# protoBoardHB.net
KiCad netlist of a schematic drawn in EAGLE
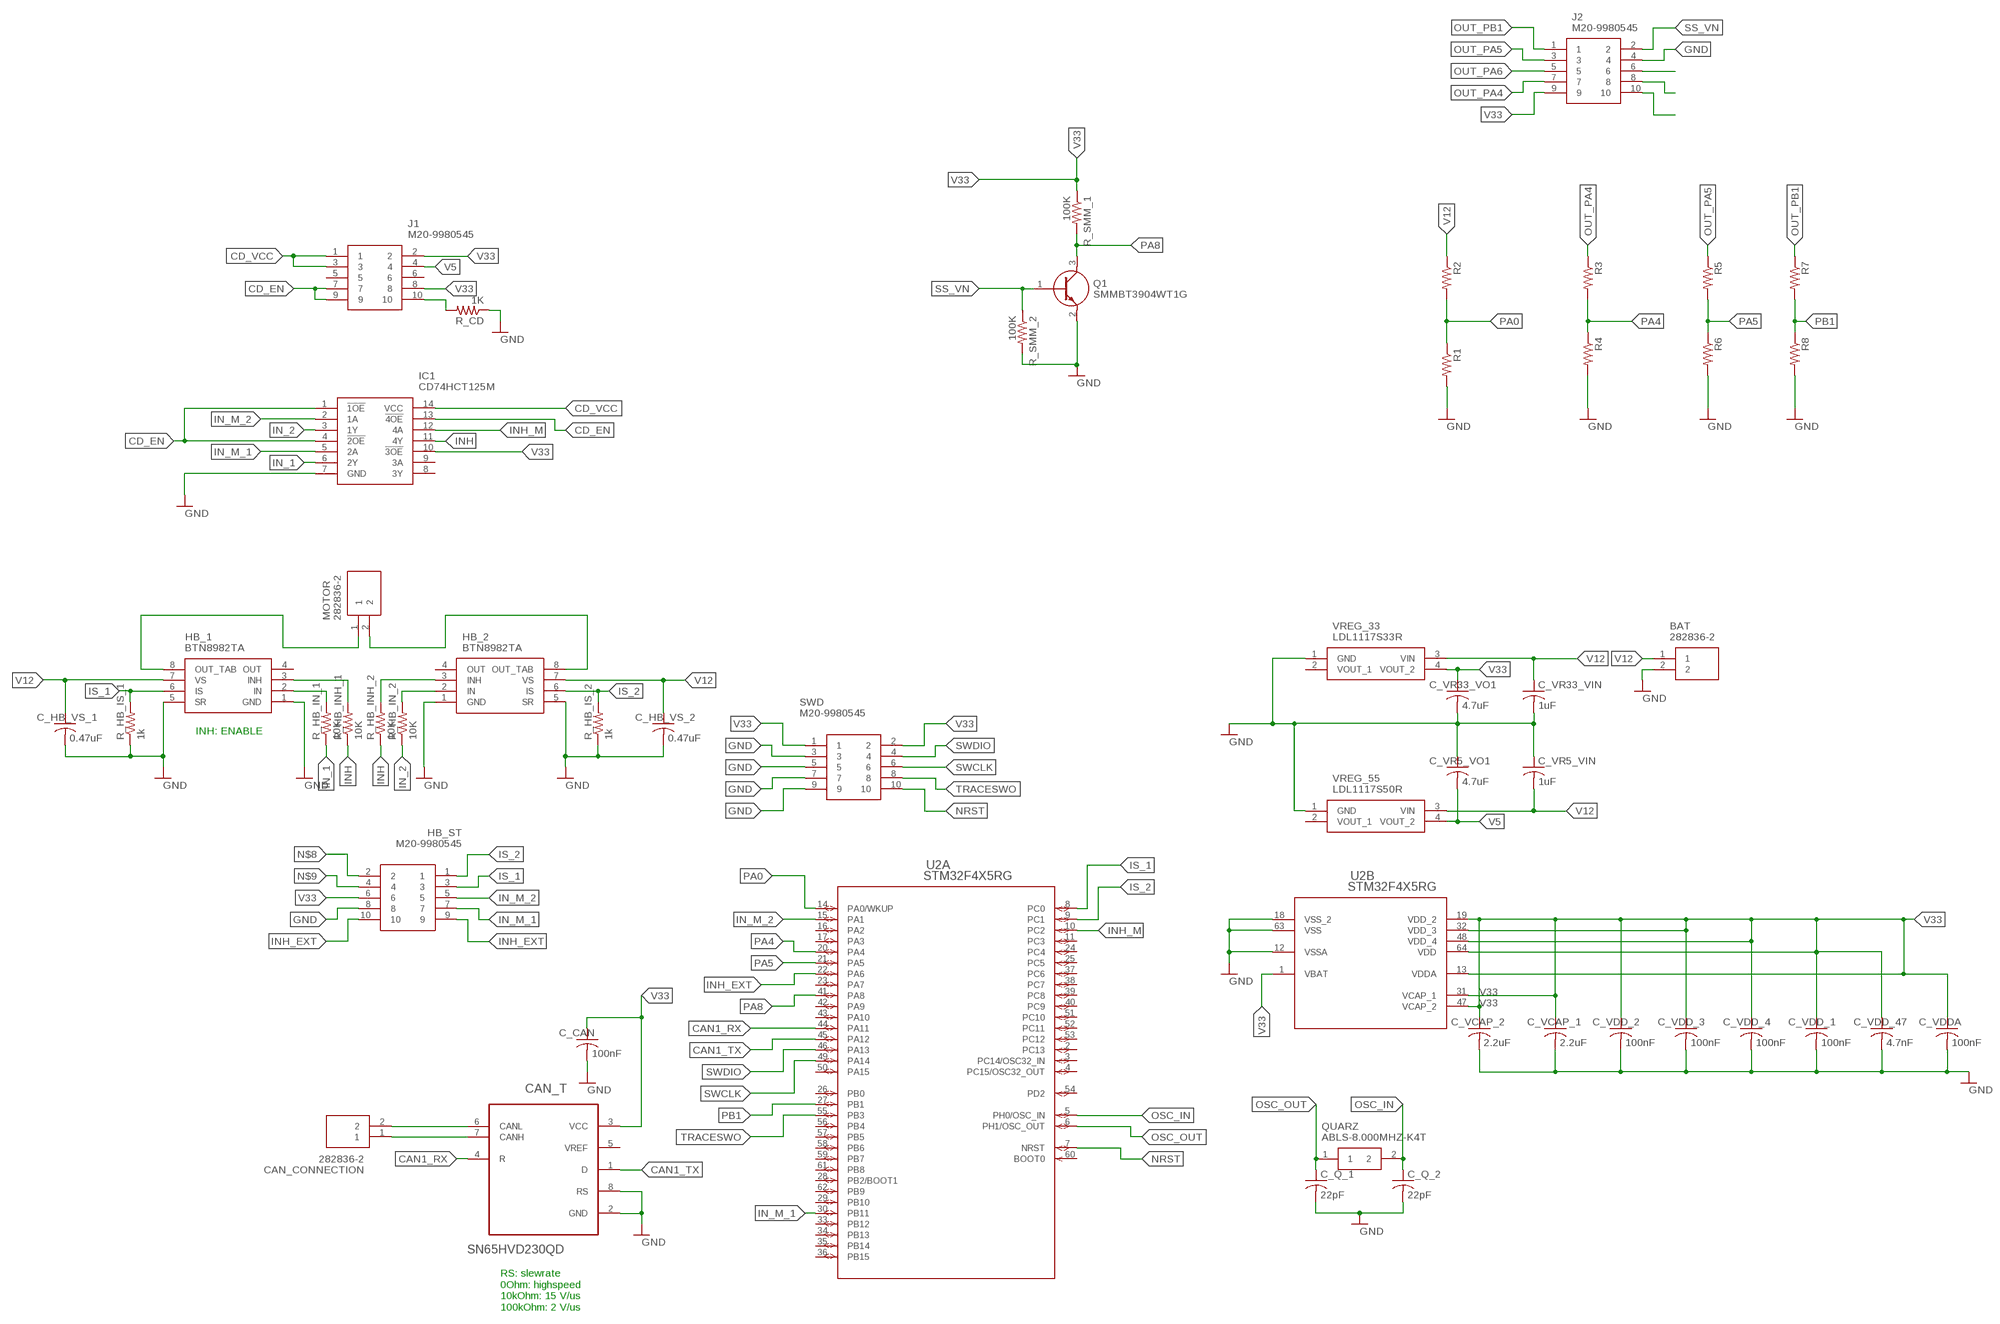
[diagram p0: schematic, sheet 1]

(export (version "E")
  (design (tool "Eeschema 10.0.6"))
  (components
    (comp (ref "BAT")
      (value "282836-2")
      (footprint "eagle-import:SHDR2W100P0X500_1X2_1000X820X1")
      (fields (field (name "MOUSER_PART_NUMBER") "571-2828362"))
      (libsource (lib "eagle-import") (part "282836-2"))
    )
    (comp (ref "CAN_CONNECTION")
      (value "282836-2")
      (footprint "eagle-import:SHDR2W100P0X500_1X2_1000X820X1")
      (fields (field (name "MOUSER_PART_NUMBER") "571-2828362"))
      (libsource (lib "eagle-import") (part "282836-2"))
    )
    (comp (ref "CAN_T")
      (value "SN65HVD230QD")
      (footprint "eagle-import:SOIC127P600X175-8N")
      (fields (field (name "MF") "TEXAS INSTRUMENTS") (field (name "MPN") "SN65HVD230QD.."))
      (libsource (lib "eagle-import") (part "SN65HVD230QD"))
    )
    (comp (ref "C_CAN")
      (value "100nF")
      (footprint "eagle-import:C1206")
      (libsource (lib "eagle-import") (part "C-USC1206"))
    )
    (comp (ref "C_HB_VS_1")
      (value "0.47uF")
      (footprint "eagle-import:C1206")
      (libsource (lib "eagle-import") (part "C-USC1206"))
    )
    (comp (ref "C_HB_VS_2")
      (value "0.47uF")
      (footprint "eagle-import:C1206")
      (libsource (lib "eagle-import") (part "C-USC1206"))
    )
    (comp (ref "C_Q_1")
      (value "22pF")
      (footprint "eagle-import:C0805")
      (libsource (lib "eagle-import") (part "C-USC0805"))
    )
    (comp (ref "C_Q_2")
      (value "22pF")
      (footprint "eagle-import:C0805")
      (libsource (lib "eagle-import") (part "C-USC0805"))
    )
    (comp (ref "C_VCAP_1")
      (value "2.2uF")
      (footprint "eagle-import:C1206")
      (libsource (lib "eagle-import") (part "C-USC1206"))
    )
    (comp (ref "C_VCAP_2")
      (value "2.2uF")
      (footprint "eagle-import:C1206")
      (libsource (lib "eagle-import") (part "C-USC1206"))
    )
    (comp (ref "C_VDDA")
      (value "100nF")
      (footprint "eagle-import:C1206")
      (libsource (lib "eagle-import") (part "C-USC1206"))
    )
    (comp (ref "C_VDD_1")
      (value "100nF")
      (footprint "eagle-import:C1206")
      (libsource (lib "eagle-import") (part "C-USC1206"))
    )
    (comp (ref "C_VDD_2")
      (value "100nF")
      (footprint "eagle-import:C1206")
      (libsource (lib "eagle-import") (part "C-USC1206"))
    )
    (comp (ref "C_VDD_3")
      (value "100nF")
      (footprint "eagle-import:C1206")
      (libsource (lib "eagle-import") (part "C-USC1206"))
    )
    (comp (ref "C_VDD_4")
      (value "100nF")
      (footprint "eagle-import:C1206")
      (libsource (lib "eagle-import") (part "C-USC1206"))
    )
    (comp (ref "C_VDD_47")
      (value "4.7nF")
      (footprint "eagle-import:C1206")
      (libsource (lib "eagle-import") (part "C-USC1206"))
    )
    (comp (ref "C_VR5_VIN")
      (value "1uF")
      (footprint "eagle-import:C1206")
      (libsource (lib "eagle-import") (part "C-USC1206"))
    )
    (comp (ref "C_VR5_VO1")
      (value "4.7uF")
      (footprint "eagle-import:C1206")
      (libsource (lib "eagle-import") (part "C-USC1206"))
    )
    (comp (ref "C_VR33_VIN")
      (value "1uF")
      (footprint "eagle-import:C1206")
      (libsource (lib "eagle-import") (part "C-USC1206"))
    )
    (comp (ref "C_VR33_VO1")
      (value "4.7uF")
      (footprint "eagle-import:C1206")
      (libsource (lib "eagle-import") (part "C-USC1206"))
    )
    (comp (ref "HB_1")
      (value "BTN8982TA")
      (footprint "eagle-import:TO127P1500X440-8N")
      (fields (field (name "MOUSER_PART_NUMBER") "726-BTN8982TA"))
      (libsource (lib "eagle-import") (part "BTN8982TA"))
    )
    (comp (ref "HB_2")
      (value "BTN8982TA")
      (footprint "eagle-import:TO127P1500X440-8N")
      (fields (field (name "MOUSER_PART_NUMBER") "726-BTN8982TA"))
      (libsource (lib "eagle-import") (part "BTN8982TA"))
    )
    (comp (ref "HB_ST")
      (value "M20-9980545")
      (footprint "eagle-import:HDRV10W80P254_2X5_1270X508X864")
      (fields (field (name "MOUSER_PART_NUMBER") "855-M20-9980545") (field (name "MF") "HARWIN"))
      (libsource (lib "eagle-import") (part "M20-9980545"))
    )
    (comp (ref "IC1")
      (value "CD74HCT125M")
      (footprint "eagle-import:SOIC127P600X175-14N")
      (fields (field (name "MOUSER_PART_NUMBER") "595-CD74HCT125M"))
      (libsource (lib "eagle-import") (part "CD74HCT125M"))
    )
    (comp (ref "J1")
      (value "M20-9980545")
      (footprint "eagle-import:HDRV10W80P254_2X5_1270X508X864")
      (fields (field (name "MOUSER_PART_NUMBER") "855-M20-9980545"))
      (libsource (lib "eagle-import") (part "M20-9980545"))
    )
    (comp (ref "J2")
      (value "M20-9980545")
      (footprint "eagle-import:HDRV10W80P254_2X5_1270X508X864")
      (fields (field (name "MOUSER_PART_NUMBER") "855-M20-9980545"))
      (libsource (lib "eagle-import") (part "M20-9980545"))
    )
    (comp (ref "MOTOR")
      (value "282836-2")
      (footprint "eagle-import:SHDR2W100P0X500_1X2_1000X820X1")
      (fields (field (name "MOUSER_PART_NUMBER") "571-2828362"))
      (libsource (lib "eagle-import") (part "282836-2"))
    )
    (comp (ref "Q1")
      (value "SMMBT3904WT1G")
      (footprint "eagle-import:SOT65P220X100-3N")
      (fields (field (name "MOUSER_PART_NUMBER") "863-SMMBT3904WT1G"))
      (libsource (lib "eagle-import") (part "SMMBT3904WT1G"))
    )
    (comp (ref "QUARZ")
      (value "ABLS-8.000MHZ-K4T")
      (footprint "eagle-import:ABLS-12.000MHZ-B2")
      (fields (field (name "MOUSER_PART_NUMBER") "815-ABLS-8.0MK4-T") (field (name "MF") "ABRACON"))
      (libsource (lib "eagle-import") (part "ABLS-8.000MHZ-K4T"))
    )
    (comp (ref "R1")
      (value "R-US_R1206")
      (footprint "eagle-import:R1206")
      (libsource (lib "eagle-import") (part "R-US_R1206"))
    )
    (comp (ref "R2")
      (value "R-US_R1206")
      (footprint "eagle-import:R1206")
      (libsource (lib "eagle-import") (part "R-US_R1206"))
    )
    (comp (ref "R3")
      (value "R-US_R1206")
      (footprint "eagle-import:R1206")
      (libsource (lib "eagle-import") (part "R-US_R1206"))
    )
    (comp (ref "R4")
      (value "R-US_R1206")
      (footprint "eagle-import:R1206")
      (libsource (lib "eagle-import") (part "R-US_R1206"))
    )
    (comp (ref "R5")
      (value "R-US_R1206")
      (footprint "eagle-import:R1206")
      (libsource (lib "eagle-import") (part "R-US_R1206"))
    )
    (comp (ref "R6")
      (value "R-US_R1206")
      (footprint "eagle-import:R1206")
      (libsource (lib "eagle-import") (part "R-US_R1206"))
    )
    (comp (ref "R7")
      (value "R-US_R1206")
      (footprint "eagle-import:R1206")
      (libsource (lib "eagle-import") (part "R-US_R1206"))
    )
    (comp (ref "R8")
      (value "R-US_R1206")
      (footprint "eagle-import:R1206")
      (libsource (lib "eagle-import") (part "R-US_R1206"))
    )
    (comp (ref "R_CD")
      (value "1K")
      (footprint "eagle-import:R1206")
      (libsource (lib "eagle-import") (part "R-US_R1206"))
    )
    (comp (ref "R_HB_INH_1")
      (value "10K")
      (footprint "eagle-import:R1206")
      (libsource (lib "eagle-import") (part "R-US_R1206"))
    )
    (comp (ref "R_HB_INH_2")
      (value "10K")
      (footprint "eagle-import:R1206")
      (libsource (lib "eagle-import") (part "R-US_R1206"))
    )
    (comp (ref "R_HB_IN_1")
      (value "10K")
      (footprint "eagle-import:R1206")
      (libsource (lib "eagle-import") (part "R-US_R1206"))
    )
    (comp (ref "R_HB_IN_2")
      (value "10K")
      (footprint "eagle-import:R1206")
      (libsource (lib "eagle-import") (part "R-US_R1206"))
    )
    (comp (ref "R_HB_IS_1")
      (value "1k")
      (footprint "eagle-import:R1206")
      (libsource (lib "eagle-import") (part "R-US_R1206"))
    )
    (comp (ref "R_HB_IS_2")
      (value "1k")
      (footprint "eagle-import:R1206")
      (libsource (lib "eagle-import") (part "R-US_R1206"))
    )
    (comp (ref "R_SMM_1")
      (value "100K")
      (footprint "eagle-import:R1206")
      (libsource (lib "eagle-import") (part "R-US_R1206"))
    )
    (comp (ref "R_SMM_2")
      (value "100K")
      (footprint "eagle-import:R1206")
      (libsource (lib "eagle-import") (part "R-US_R1206"))
    )
    (comp (ref "SWD")
      (value "M20-9980545")
      (footprint "eagle-import:HDRV10W80P254_2X5_1270X508X864")
      (fields (field (name "MOUSER_PART_NUMBER") "855-M20-9980545") (field (name "MF") "HARWIN"))
      (libsource (lib "eagle-import") (part "M20-9980545"))
    )
    (comp (ref "U2")
      (value "STM32F4X5RG")
      (footprint "eagle-import:LQFP64-10X10MM")
      (fields (field (name "OC_FARNELL") "unknown"))
      (libsource (lib "eagle-import") (part "STM32F4X5RG"))
    )
    (comp (ref "VREG_33")
      (value "LDL1117S33R")
      (footprint "eagle-import:SOT230P700X180-4N")
      (fields (field (name "MOUSER_PART_NUMBER") "511-LDL1117S33R") (field (name "MF") "STMICROELECTRONICS"))
      (libsource (lib "eagle-import") (part "LDL1117S33R"))
    )
    (comp (ref "VREG_55")
      (value "LDL1117S50R")
      (footprint "eagle-import:SOT230P700X180-4N")
      (fields (field (name "MOUSER_PART_NUMBER") "511-LDL1117S50R") (field (name "MF") "STMICROELECTRONICS"))
      (libsource (lib "eagle-import") (part "LDL1117S50R"))
    )
  )
  (nets
    (net (code "1") (name "CAN1_RX") (class "Default")
      (node (ref "CAN_T") (pin "4") (pinfunction "R_4") (pintype "output"))
      (node (ref "U2") (pin "44") (pinfunction "PA11_44") (pintype "bidirectional"))
    )
    (net (code "2") (name "CAN1_TX") (class "Default")
      (node (ref "CAN_T") (pin "1") (pinfunction "D_1") (pintype "input"))
      (node (ref "U2") (pin "45") (pinfunction "PA12_45") (pintype "bidirectional"))
    )
    (net (code "3") (name "CD_EN") (class "Default")
      (node (ref "IC1") (pin "1") (pinfunction "~{1OE}_1") (pintype "bidirectional"))
      (node (ref "IC1") (pin "13") (pinfunction "~{4OE}_13") (pintype "bidirectional"))
      (node (ref "IC1") (pin "4") (pinfunction "~{2OE}_4") (pintype "bidirectional"))
      (node (ref "J1") (pin "7") (pinfunction "7_7") (pintype "bidirectional"))
      (node (ref "J1") (pin "9") (pinfunction "9_9") (pintype "bidirectional"))
    )
    (net (code "4") (name "CD_VCC") (class "Default")
      (node (ref "IC1") (pin "14") (pinfunction "VCC_14") (pintype "power_in"))
      (node (ref "J1") (pin "1") (pinfunction "1_1") (pintype "bidirectional"))
      (node (ref "J1") (pin "3") (pinfunction "3_3") (pintype "bidirectional"))
    )
    (net (code "5") (name "GND") (class "Default")
      (node (ref "BAT") (pin "2") (pinfunction "2_2") (pintype "bidirectional"))
      (node (ref "CAN_T") (pin "2") (pinfunction "GND_2") (pintype "passive"))
      (node (ref "CAN_T") (pin "8") (pinfunction "RS_8") (pintype "input"))
      (node (ref "C_CAN") (pin "2") (pinfunction "2_2") (pintype "passive"))
      (node (ref "C_HB_VS_1") (pin "2") (pinfunction "2_2") (pintype "passive"))
      (node (ref "C_HB_VS_2") (pin "2") (pinfunction "2_2") (pintype "passive"))
      (node (ref "C_Q_1") (pin "2") (pinfunction "2_2") (pintype "passive"))
      (node (ref "C_Q_2") (pin "2") (pinfunction "2_2") (pintype "passive"))
      (node (ref "C_VCAP_1") (pin "2") (pinfunction "2_2") (pintype "passive"))
      (node (ref "C_VCAP_2") (pin "2") (pinfunction "2_2") (pintype "passive"))
      (node (ref "C_VDDA") (pin "2") (pinfunction "2_2") (pintype "passive"))
      (node (ref "C_VDD_1") (pin "2") (pinfunction "2_2") (pintype "passive"))
      (node (ref "C_VDD_2") (pin "2") (pinfunction "2_2") (pintype "passive"))
      (node (ref "C_VDD_3") (pin "2") (pinfunction "2_2") (pintype "passive"))
      (node (ref "C_VDD_4") (pin "2") (pinfunction "2_2") (pintype "passive"))
      (node (ref "C_VDD_47") (pin "2") (pinfunction "2_2") (pintype "passive"))
      (node (ref "C_VR33_VIN") (pin "2") (pinfunction "2_2") (pintype "passive"))
      (node (ref "C_VR33_VO1") (pin "2") (pinfunction "2_2") (pintype "passive"))
      (node (ref "C_VR5_VIN") (pin "1") (pinfunction "1_1") (pintype "passive"))
      (node (ref "C_VR5_VO1") (pin "1") (pinfunction "1_1") (pintype "passive"))
      (node (ref "HB_1") (pin "1") (pinfunction "GND_1") (pintype "power_in"))
      (node (ref "HB_1") (pin "5") (pinfunction "SR_5") (pintype "bidirectional"))
      (node (ref "HB_2") (pin "1") (pinfunction "GND_1") (pintype "power_in"))
      (node (ref "HB_2") (pin "5") (pinfunction "SR_5") (pintype "bidirectional"))
      (node (ref "HB_ST") (pin "8") (pinfunction "8_8") (pintype "bidirectional"))
      (node (ref "IC1") (pin "7") (pinfunction "GND_7") (pintype "power_in"))
      (node (ref "J2") (pin "4") (pinfunction "4_4") (pintype "bidirectional"))
      (node (ref "Q1") (pin "2") (pinfunction "E_2") (pintype "bidirectional"))
      (node (ref "R1") (pin "2") (pinfunction "2_2") (pintype "passive"))
      (node (ref "R4") (pin "2") (pinfunction "2_2") (pintype "passive"))
      (node (ref "R6") (pin "2") (pinfunction "2_2") (pintype "passive"))
      (node (ref "R8") (pin "2") (pinfunction "2_2") (pintype "passive"))
      (node (ref "R_CD") (pin "1") (pinfunction "1_1") (pintype "passive"))
      (node (ref "R_HB_IS_1") (pin "1") (pinfunction "1_1") (pintype "passive"))
      (node (ref "R_HB_IS_2") (pin "1") (pinfunction "1_1") (pintype "passive"))
      (node (ref "R_SMM_2") (pin "2") (pinfunction "2_2") (pintype "passive"))
      (node (ref "SWD") (pin "3") (pinfunction "3_3") (pintype "bidirectional"))
      (node (ref "SWD") (pin "5") (pinfunction "5_5") (pintype "bidirectional"))
      (node (ref "SWD") (pin "7") (pinfunction "7_7") (pintype "bidirectional"))
      (node (ref "SWD") (pin "9") (pinfunction "9_9") (pintype "bidirectional"))
      (node (ref "U2") (pin "12") (pinfunction "VSSA_12") (pintype "power_in"))
      (node (ref "U2") (pin "18") (pinfunction "VSS_2_18") (pintype "power_in"))
      (node (ref "U2") (pin "63") (pinfunction "VSS_63") (pintype "power_in"))
      (node (ref "VREG_33") (pin "1") (pinfunction "GND_1") (pintype "power_in"))
      (node (ref "VREG_55") (pin "1") (pinfunction "GND_1") (pintype "bidirectional"))
    )
    (net (code "6") (name "INH") (class "Default")
      (node (ref "IC1") (pin "11") (pinfunction "4Y_11") (pintype "bidirectional"))
      (node (ref "R_HB_INH_1") (pin "1") (pinfunction "1_1") (pintype "passive"))
      (node (ref "R_HB_INH_2") (pin "1") (pinfunction "1_1") (pintype "passive"))
    )
    (net (code "7") (name "INH_EXT") (class "Default")
      (node (ref "HB_ST") (pin "10") (pinfunction "10_10") (pintype "bidirectional"))
      (node (ref "HB_ST") (pin "9") (pinfunction "9_9") (pintype "bidirectional"))
      (node (ref "U2") (pin "22") (pinfunction "PA6_22") (pintype "bidirectional"))
    )
    (net (code "8") (name "INH_M") (class "Default")
      (node (ref "IC1") (pin "12") (pinfunction "4A_12") (pintype "bidirectional"))
      (node (ref "U2") (pin "10") (pinfunction "PC2_10") (pintype "bidirectional"))
    )
    (net (code "9") (name "IN_1") (class "Default")
      (node (ref "IC1") (pin "6") (pinfunction "2Y_6") (pintype "bidirectional"))
      (node (ref "R_HB_IN_1") (pin "1") (pinfunction "1_1") (pintype "passive"))
    )
    (net (code "10") (name "IN_2") (class "Default")
      (node (ref "IC1") (pin "3") (pinfunction "1Y_3") (pintype "bidirectional"))
      (node (ref "R_HB_IN_2") (pin "1") (pinfunction "1_1") (pintype "passive"))
    )
    (net (code "11") (name "IN_M_1") (class "Default")
      (node (ref "HB_ST") (pin "7") (pinfunction "7_7") (pintype "bidirectional"))
      (node (ref "IC1") (pin "5") (pinfunction "2A_5") (pintype "bidirectional"))
      (node (ref "U2") (pin "30") (pinfunction "PB11_30") (pintype "bidirectional"))
    )
    (net (code "12") (name "IN_M_2") (class "Default")
      (node (ref "HB_ST") (pin "5") (pinfunction "5_5") (pintype "bidirectional"))
      (node (ref "IC1") (pin "2") (pinfunction "1A_2") (pintype "bidirectional"))
      (node (ref "U2") (pin "15") (pinfunction "PA1_15") (pintype "bidirectional"))
    )
    (net (code "13") (name "IS_1") (class "Default")
      (node (ref "HB_1") (pin "6") (pinfunction "IS_6") (pintype "bidirectional"))
      (node (ref "HB_ST") (pin "3") (pinfunction "3_3") (pintype "bidirectional"))
      (node (ref "R_HB_IS_1") (pin "2") (pinfunction "2_2") (pintype "passive"))
      (node (ref "U2") (pin "8") (pinfunction "PC0_8") (pintype "bidirectional"))
    )
    (net (code "14") (name "IS_2") (class "Default")
      (node (ref "HB_2") (pin "6") (pinfunction "IS_6") (pintype "bidirectional"))
      (node (ref "HB_ST") (pin "1") (pinfunction "1_1") (pintype "bidirectional"))
      (node (ref "R_HB_IS_2") (pin "2") (pinfunction "2_2") (pintype "passive"))
      (node (ref "U2") (pin "9") (pinfunction "PC1_9") (pintype "bidirectional"))
    )
    (net (code "15") (name "N$8") (class "Default")
      (node (ref "HB_ST") (pin "2") (pinfunction "2_2") (pintype "bidirectional"))
    )
    (net (code "16") (name "N$9") (class "Default")
      (node (ref "HB_ST") (pin "4") (pinfunction "4_4") (pintype "bidirectional"))
    )
    (net (code "17") (name "NRST") (class "Default")
      (node (ref "SWD") (pin "10") (pinfunction "10_10") (pintype "bidirectional"))
      (node (ref "U2") (pin "7") (pinfunction "NRST_7") (pintype "bidirectional"))
    )
    (net (code "18") (name "Net-(CAN_T-CANH)") (class "Default")
      (node (ref "CAN_CONNECTION") (pin "1") (pinfunction "1_1") (pintype "bidirectional"))
      (node (ref "CAN_T") (pin "7") (pinfunction "CANH_7") (pintype "output"))
    )
    (net (code "19") (name "Net-(CAN_T-CANL)") (class "Default")
      (node (ref "CAN_CONNECTION") (pin "2") (pinfunction "2_2") (pintype "bidirectional"))
      (node (ref "CAN_T") (pin "6") (pinfunction "CANL_6") (pintype "output"))
    )
    (net (code "20") (name "Net-(HB_1-IN)") (class "Default")
      (node (ref "HB_1") (pin "2") (pinfunction "IN_2") (pintype "input"))
      (node (ref "R_HB_IN_1") (pin "2") (pinfunction "2_2") (pintype "passive"))
    )
    (net (code "21") (name "Net-(HB_1-INH)") (class "Default")
      (node (ref "HB_1") (pin "3") (pinfunction "INH_3") (pintype "input"))
      (node (ref "R_HB_INH_1") (pin "2") (pinfunction "2_2") (pintype "passive"))
    )
    (net (code "22") (name "Net-(HB_1-OUT_TAB)") (class "Default")
      (node (ref "HB_1") (pin "8") (pinfunction "OUT_TAB_8") (pintype "output"))
      (node (ref "MOTOR") (pin "1") (pinfunction "1_1") (pintype "bidirectional"))
    )
    (net (code "23") (name "Net-(HB_2-IN)") (class "Default")
      (node (ref "HB_2") (pin "2") (pinfunction "IN_2") (pintype "input"))
      (node (ref "R_HB_IN_2") (pin "2") (pinfunction "2_2") (pintype "passive"))
    )
    (net (code "24") (name "Net-(HB_2-INH)") (class "Default")
      (node (ref "HB_2") (pin "3") (pinfunction "INH_3") (pintype "input"))
      (node (ref "R_HB_INH_2") (pin "2") (pinfunction "2_2") (pintype "passive"))
    )
    (net (code "25") (name "Net-(HB_2-OUT_TAB)") (class "Default")
      (node (ref "HB_2") (pin "8") (pinfunction "OUT_TAB_8") (pintype "output"))
      (node (ref "MOTOR") (pin "2") (pinfunction "2_2") (pintype "bidirectional"))
    )
    (net (code "26") (name "Net-(J1-Pad10)") (class "Default")
      (node (ref "J1") (pin "10") (pinfunction "10_10") (pintype "bidirectional"))
      (node (ref "R_CD") (pin "2") (pinfunction "2_2") (pintype "passive"))
    )
    (net (code "27") (name "OSC_IN") (class "Default")
      (node (ref "C_Q_2") (pin "1") (pinfunction "1_1") (pintype "passive"))
      (node (ref "QUARZ") (pin "2") (pinfunction "2_2") (pintype "bidirectional"))
      (node (ref "U2") (pin "5") (pinfunction "PH0/OSC_IN_5") (pintype "bidirectional"))
    )
    (net (code "28") (name "OSC_OUT") (class "Default")
      (node (ref "C_Q_1") (pin "1") (pinfunction "1_1") (pintype "passive"))
      (node (ref "QUARZ") (pin "1") (pinfunction "1_1") (pintype "bidirectional"))
      (node (ref "U2") (pin "6") (pinfunction "PH1/OSC_OUT_6") (pintype "bidirectional"))
    )
    (net (code "29") (name "OUT_PA4") (class "Default")
      (node (ref "J2") (pin "7") (pinfunction "7_7") (pintype "bidirectional"))
      (node (ref "R3") (pin "1") (pinfunction "1_1") (pintype "passive"))
    )
    (net (code "30") (name "OUT_PA5") (class "Default")
      (node (ref "J2") (pin "3") (pinfunction "3_3") (pintype "bidirectional"))
      (node (ref "R5") (pin "1") (pinfunction "1_1") (pintype "passive"))
    )
    (net (code "31") (name "OUT_PA6") (class "Default")
      (node (ref "J2") (pin "5") (pinfunction "5_5") (pintype "bidirectional"))
    )
    (net (code "32") (name "OUT_PB1") (class "Default")
      (node (ref "J2") (pin "1") (pinfunction "1_1") (pintype "bidirectional"))
      (node (ref "R7") (pin "1") (pinfunction "1_1") (pintype "passive"))
    )
    (net (code "33") (name "PA0") (class "Default")
      (node (ref "R1") (pin "1") (pinfunction "1_1") (pintype "passive"))
      (node (ref "R2") (pin "2") (pinfunction "2_2") (pintype "passive"))
      (node (ref "U2") (pin "14") (pinfunction "PA0/WKUP_14") (pintype "bidirectional"))
    )
    (net (code "34") (name "PA4") (class "Default")
      (node (ref "R3") (pin "2") (pinfunction "2_2") (pintype "passive"))
      (node (ref "R4") (pin "1") (pinfunction "1_1") (pintype "passive"))
      (node (ref "U2") (pin "20") (pinfunction "PA4_20") (pintype "bidirectional"))
    )
    (net (code "35") (name "PA5") (class "Default")
      (node (ref "R5") (pin "2") (pinfunction "2_2") (pintype "passive"))
      (node (ref "R6") (pin "1") (pinfunction "1_1") (pintype "passive"))
      (node (ref "U2") (pin "21") (pinfunction "PA5_21") (pintype "bidirectional"))
    )
    (net (code "36") (name "PA8") (class "Default")
      (node (ref "Q1") (pin "3") (pinfunction "C_3") (pintype "bidirectional"))
      (node (ref "R_SMM_1") (pin "2") (pinfunction "2_2") (pintype "passive"))
      (node (ref "U2") (pin "41") (pinfunction "PA8_41") (pintype "bidirectional"))
    )
    (net (code "37") (name "PB1") (class "Default")
      (node (ref "R7") (pin "2") (pinfunction "2_2") (pintype "passive"))
      (node (ref "R8") (pin "1") (pinfunction "1_1") (pintype "passive"))
      (node (ref "U2") (pin "27") (pinfunction "PB1_27") (pintype "bidirectional"))
    )
    (net (code "38") (name "SS_VN") (class "Default")
      (node (ref "J2") (pin "2") (pinfunction "2_2") (pintype "bidirectional"))
      (node (ref "Q1") (pin "1") (pinfunction "B_1") (pintype "bidirectional"))
      (node (ref "R_SMM_2") (pin "1") (pinfunction "1_1") (pintype "passive"))
    )
    (net (code "39") (name "SWCLK") (class "Default")
      (node (ref "SWD") (pin "6") (pinfunction "6_6") (pintype "bidirectional"))
      (node (ref "U2") (pin "49") (pinfunction "PA14_49") (pintype "bidirectional"))
    )
    (net (code "40") (name "SWDIO") (class "Default")
      (node (ref "SWD") (pin "4") (pinfunction "4_4") (pintype "bidirectional"))
      (node (ref "U2") (pin "46") (pinfunction "PA13_46") (pintype "bidirectional"))
    )
    (net (code "41") (name "TRACESWO") (class "Default")
      (node (ref "SWD") (pin "8") (pinfunction "8_8") (pintype "bidirectional"))
      (node (ref "U2") (pin "55") (pinfunction "PB3_55") (pintype "bidirectional"))
    )
    (net (code "42") (name "V5") (class "Default")
      (node (ref "C_VR5_VO1") (pin "2") (pinfunction "2_2") (pintype "passive"))
      (node (ref "J1") (pin "4") (pinfunction "4_4") (pintype "bidirectional"))
      (node (ref "VREG_55") (pin "4") (pinfunction "VOUT_2_4") (pintype "bidirectional"))
    )
    (net (code "43") (name "V12") (class "Default")
      (node (ref "BAT") (pin "1") (pinfunction "1_1") (pintype "bidirectional"))
      (node (ref "C_HB_VS_1") (pin "1") (pinfunction "1_1") (pintype "passive"))
      (node (ref "C_HB_VS_2") (pin "1") (pinfunction "1_1") (pintype "passive"))
      (node (ref "C_VR33_VIN") (pin "1") (pinfunction "1_1") (pintype "passive"))
      (node (ref "C_VR5_VIN") (pin "2") (pinfunction "2_2") (pintype "passive"))
      (node (ref "HB_1") (pin "7") (pinfunction "VS_7") (pintype "bidirectional"))
      (node (ref "HB_2") (pin "7") (pinfunction "VS_7") (pintype "bidirectional"))
      (node (ref "R2") (pin "1") (pinfunction "1_1") (pintype "passive"))
      (node (ref "VREG_33") (pin "3") (pinfunction "VIN_3") (pintype "input"))
      (node (ref "VREG_55") (pin "3") (pinfunction "VIN_3") (pintype "bidirectional"))
    )
    (net (code "44") (name "V33") (class "Default")
      (node (ref "CAN_T") (pin "3") (pinfunction "VCC_3") (pintype "power_in"))
      (node (ref "C_CAN") (pin "1") (pinfunction "1_1") (pintype "passive"))
      (node (ref "C_VCAP_1") (pin "1") (pinfunction "1_1") (pintype "passive"))
      (node (ref "C_VCAP_2") (pin "1") (pinfunction "1_1") (pintype "passive"))
      (node (ref "C_VDDA") (pin "1") (pinfunction "1_1") (pintype "passive"))
      (node (ref "C_VDD_1") (pin "1") (pinfunction "1_1") (pintype "passive"))
      (node (ref "C_VDD_2") (pin "1") (pinfunction "1_1") (pintype "passive"))
      (node (ref "C_VDD_3") (pin "1") (pinfunction "1_1") (pintype "passive"))
      (node (ref "C_VDD_4") (pin "1") (pinfunction "1_1") (pintype "passive"))
      (node (ref "C_VDD_47") (pin "1") (pinfunction "1_1") (pintype "passive"))
      (node (ref "C_VR33_VO1") (pin "1") (pinfunction "1_1") (pintype "passive"))
      (node (ref "HB_ST") (pin "6") (pinfunction "6_6") (pintype "bidirectional"))
      (node (ref "IC1") (pin "10") (pinfunction "~{3OE}_10") (pintype "bidirectional"))
      (node (ref "J1") (pin "2") (pinfunction "2_2") (pintype "bidirectional"))
      (node (ref "J1") (pin "8") (pinfunction "8_8") (pintype "bidirectional"))
      (node (ref "J2") (pin "9") (pinfunction "9_9") (pintype "bidirectional"))
      (node (ref "R_SMM_1") (pin "1") (pinfunction "1_1") (pintype "passive"))
      (node (ref "SWD") (pin "1") (pinfunction "1_1") (pintype "bidirectional"))
      (node (ref "SWD") (pin "2") (pinfunction "2_2") (pintype "bidirectional"))
      (node (ref "U2") (pin "1") (pinfunction "VBAT_1") (pintype "power_in"))
      (node (ref "U2") (pin "13") (pinfunction "VDDA_13") (pintype "power_in"))
      (node (ref "U2") (pin "19") (pinfunction "VDD_2_19") (pintype "power_in"))
      (node (ref "U2") (pin "31") (pinfunction "VCAP_1_31") (pintype "power_in"))
      (node (ref "U2") (pin "32") (pinfunction "VDD_3_32") (pintype "power_in"))
      (node (ref "U2") (pin "47") (pinfunction "VCAP_2_47") (pintype "power_in"))
      (node (ref "U2") (pin "48") (pinfunction "VDD_4_48") (pintype "power_in"))
      (node (ref "U2") (pin "64") (pinfunction "VDD_64") (pintype "power_in"))
      (node (ref "VREG_33") (pin "4") (pinfunction "VOUT_2_4") (pintype "output"))
    )
    (net (code "45") (name "unconnected-(CAN_T-VREF-Pad5)") (class "Default")
      (node (ref "CAN_T") (pin "5") (pinfunction "VREF_5") (pintype "input"))
    )
    (net (code "46") (name "unconnected-(HB_1-OUT-Pad4)") (class "Default")
      (node (ref "HB_1") (pin "4") (pinfunction "OUT_4") (pintype "output"))
    )
    (net (code "47") (name "unconnected-(HB_2-OUT-Pad4)") (class "Default")
      (node (ref "HB_2") (pin "4") (pinfunction "OUT_4") (pintype "output"))
    )
    (net (code "48") (name "unconnected-(IC1-3A-Pad9)") (class "Default")
      (node (ref "IC1") (pin "9") (pinfunction "3A_9") (pintype "bidirectional"))
    )
    (net (code "49") (name "unconnected-(IC1-3Y-Pad8)") (class "Default")
      (node (ref "IC1") (pin "8") (pinfunction "3Y_8") (pintype "bidirectional"))
    )
    (net (code "50") (name "unconnected-(J1-Pad5)") (class "Default")
      (node (ref "J1") (pin "5") (pinfunction "5_5") (pintype "bidirectional"))
    )
    (net (code "51") (name "unconnected-(J1-Pad6)") (class "Default")
      (node (ref "J1") (pin "6") (pinfunction "6_6") (pintype "bidirectional"))
    )
    (net (code "52") (name "unconnected-(J2-Pad6)") (class "Default")
      (node (ref "J2") (pin "6") (pinfunction "6_6") (pintype "bidirectional"))
    )
    (net (code "53") (name "unconnected-(J2-Pad8)") (class "Default")
      (node (ref "J2") (pin "8") (pinfunction "8_8") (pintype "bidirectional"))
    )
    (net (code "54") (name "unconnected-(J2-Pad10)") (class "Default")
      (node (ref "J2") (pin "10") (pinfunction "10_10") (pintype "bidirectional"))
    )
    (net (code "55") (name "unconnected-(U2A-BOOT0-Pad60)") (class "Default")
      (node (ref "U2") (pin "60") (pinfunction "BOOT0_60") (pintype "input"))
    )
    (net (code "56") (name "unconnected-(U2A-PA2-Pad16)") (class "Default")
      (node (ref "U2") (pin "16") (pinfunction "PA2_16") (pintype "bidirectional"))
    )
    (net (code "57") (name "unconnected-(U2A-PA3-Pad17)") (class "Default")
      (node (ref "U2") (pin "17") (pinfunction "PA3_17") (pintype "bidirectional"))
    )
    (net (code "58") (name "unconnected-(U2A-PA7-Pad23)") (class "Default")
      (node (ref "U2") (pin "23") (pinfunction "PA7_23") (pintype "bidirectional"))
    )
    (net (code "59") (name "unconnected-(U2A-PA9-Pad42)") (class "Default")
      (node (ref "U2") (pin "42") (pinfunction "PA9_42") (pintype "bidirectional"))
    )
    (net (code "60") (name "unconnected-(U2A-PA10-Pad43)") (class "Default")
      (node (ref "U2") (pin "43") (pinfunction "PA10_43") (pintype "bidirectional"))
    )
    (net (code "61") (name "unconnected-(U2A-PA15-Pad50)") (class "Default")
      (node (ref "U2") (pin "50") (pinfunction "PA15_50") (pintype "bidirectional"))
    )
    (net (code "62") (name "unconnected-(U2A-PB0-Pad26)") (class "Default")
      (node (ref "U2") (pin "26") (pinfunction "PB0_26") (pintype "bidirectional"))
    )
    (net (code "63") (name "unconnected-(U2A-PB2{slash}BOOT1-Pad28)") (class "Default")
      (node (ref "U2") (pin "28") (pinfunction "PB2/BOOT1_28") (pintype "bidirectional"))
    )
    (net (code "64") (name "unconnected-(U2A-PB4-Pad56)") (class "Default")
      (node (ref "U2") (pin "56") (pinfunction "PB4_56") (pintype "bidirectional"))
    )
    (net (code "65") (name "unconnected-(U2A-PB5-Pad57)") (class "Default")
      (node (ref "U2") (pin "57") (pinfunction "PB5_57") (pintype "bidirectional"))
    )
    (net (code "66") (name "unconnected-(U2A-PB6-Pad58)") (class "Default")
      (node (ref "U2") (pin "58") (pinfunction "PB6_58") (pintype "bidirectional"))
    )
    (net (code "67") (name "unconnected-(U2A-PB7-Pad59)") (class "Default")
      (node (ref "U2") (pin "59") (pinfunction "PB7_59") (pintype "bidirectional"))
    )
    (net (code "68") (name "unconnected-(U2A-PB8-Pad61)") (class "Default")
      (node (ref "U2") (pin "61") (pinfunction "PB8_61") (pintype "bidirectional"))
    )
    (net (code "69") (name "unconnected-(U2A-PB9-Pad62)") (class "Default")
      (node (ref "U2") (pin "62") (pinfunction "PB9_62") (pintype "bidirectional"))
    )
    (net (code "70") (name "unconnected-(U2A-PB10-Pad29)") (class "Default")
      (node (ref "U2") (pin "29") (pinfunction "PB10_29") (pintype "bidirectional"))
    )
    (net (code "71") (name "unconnected-(U2A-PB12-Pad33)") (class "Default")
      (node (ref "U2") (pin "33") (pinfunction "PB12_33") (pintype "bidirectional"))
    )
    (net (code "72") (name "unconnected-(U2A-PB13-Pad34)") (class "Default")
      (node (ref "U2") (pin "34") (pinfunction "PB13_34") (pintype "bidirectional"))
    )
    (net (code "73") (name "unconnected-(U2A-PB14-Pad35)") (class "Default")
      (node (ref "U2") (pin "35") (pinfunction "PB14_35") (pintype "bidirectional"))
    )
    (net (code "74") (name "unconnected-(U2A-PB15-Pad36)") (class "Default")
      (node (ref "U2") (pin "36") (pinfunction "PB15_36") (pintype "bidirectional"))
    )
    (net (code "75") (name "unconnected-(U2A-PC3-Pad11)") (class "Default")
      (node (ref "U2") (pin "11") (pinfunction "PC3_11") (pintype "bidirectional"))
    )
    (net (code "76") (name "unconnected-(U2A-PC4-Pad24)") (class "Default")
      (node (ref "U2") (pin "24") (pinfunction "PC4_24") (pintype "bidirectional"))
    )
    (net (code "77") (name "unconnected-(U2A-PC5-Pad25)") (class "Default")
      (node (ref "U2") (pin "25") (pinfunction "PC5_25") (pintype "bidirectional"))
    )
    (net (code "78") (name "unconnected-(U2A-PC6-Pad37)") (class "Default")
      (node (ref "U2") (pin "37") (pinfunction "PC6_37") (pintype "bidirectional"))
    )
    (net (code "79") (name "unconnected-(U2A-PC7-Pad38)") (class "Default")
      (node (ref "U2") (pin "38") (pinfunction "PC7_38") (pintype "bidirectional"))
    )
    (net (code "80") (name "unconnected-(U2A-PC8-Pad39)") (class "Default")
      (node (ref "U2") (pin "39") (pinfunction "PC8_39") (pintype "bidirectional"))
    )
    (net (code "81") (name "unconnected-(U2A-PC9-Pad40)") (class "Default")
      (node (ref "U2") (pin "40") (pinfunction "PC9_40") (pintype "bidirectional"))
    )
    (net (code "82") (name "unconnected-(U2A-PC10-Pad51)") (class "Default")
      (node (ref "U2") (pin "51") (pinfunction "PC10_51") (pintype "bidirectional"))
    )
    (net (code "83") (name "unconnected-(U2A-PC11-Pad52)") (class "Default")
      (node (ref "U2") (pin "52") (pinfunction "PC11_52") (pintype "bidirectional"))
    )
    (net (code "84") (name "unconnected-(U2A-PC12-Pad53)") (class "Default")
      (node (ref "U2") (pin "53") (pinfunction "PC12_53") (pintype "bidirectional"))
    )
    (net (code "85") (name "unconnected-(U2A-PC13-Pad2)") (class "Default")
      (node (ref "U2") (pin "2") (pinfunction "PC13_2") (pintype "bidirectional"))
    )
    (net (code "86") (name "unconnected-(U2A-PC14{slash}OSC32_IN-Pad3)") (class "Default")
      (node (ref "U2") (pin "3") (pinfunction "PC14/OSC32_IN_3") (pintype "bidirectional"))
    )
    (net (code "87") (name "unconnected-(U2A-PC15{slash}OSC32_OUT-Pad4)") (class "Default")
      (node (ref "U2") (pin "4") (pinfunction "PC15/OSC32_OUT_4") (pintype "bidirectional"))
    )
    (net (code "88") (name "unconnected-(U2A-PD2-Pad54)") (class "Default")
      (node (ref "U2") (pin "54") (pinfunction "PD2_54") (pintype "bidirectional"))
    )
    (net (code "89") (name "unconnected-(VREG_33-VOUT_1-Pad2)") (class "Default")
      (node (ref "VREG_33") (pin "2") (pinfunction "VOUT_1_2") (pintype "output"))
    )
    (net (code "90") (name "unconnected-(VREG_55-VOUT_1-Pad2)") (class "Default")
      (node (ref "VREG_55") (pin "2") (pinfunction "VOUT_1_2") (pintype "bidirectional"))
    )
  )
)
